# Reid_Orthotic_v2_PWR.net
KiCad netlist of a schematic drawn in Altium Designer
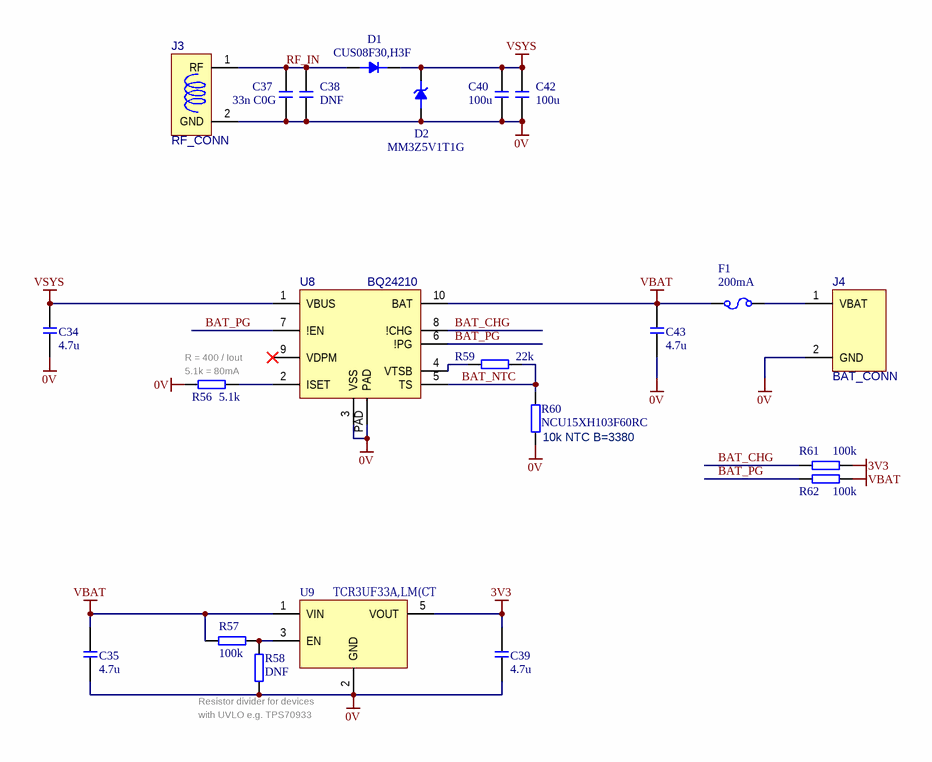
[diagram p0: Reid Orthotic v2 PWR.SchDoc]

(export (version "E")
  (design (tool "Eeschema 10.0.6"))
  (components
    (comp (ref "C34")
      (value "4.7u")
      (footprint "0603 CAP HD")
      (libsource (lib "zoo589 PCB Library") (part "Capacitor"))
    )
    (comp (ref "C35")
      (value "4.7u")
      (footprint "0603 CAP HD")
      (libsource (lib "zoo589 PCB Library") (part "Capacitor"))
    )
    (comp (ref "C37")
      (value "33n C0G")
      (footprint "0805 CAP")
      (libsource (lib "zoo589 PCB Library") (part "Capacitor"))
    )
    (comp (ref "C38")
      (value "DNF")
      (footprint "0805 CAP")
      (libsource (lib "zoo589 PCB Library") (part "Capacitor"))
    )
    (comp (ref "C39")
      (value "4.7u")
      (footprint "0603 CAP HD")
      (libsource (lib "zoo589 PCB Library") (part "Capacitor"))
    )
    (comp (ref "C40")
      (value "100u")
      (footprint "0805 CAP")
      (libsource (lib "zoo589 PCB Library") (part "Capacitor"))
    )
    (comp (ref "C42")
      (value "100u")
      (footprint "0805 CAP")
      (libsource (lib "zoo589 PCB Library") (part "Capacitor"))
    )
    (comp (ref "C43")
      (value "4.7u")
      (footprint "0603 CAP HD")
      (libsource (lib "zoo589 PCB Library") (part "Capacitor"))
    )
    (comp (ref "D1")
      (value "CUS08F30,H3F")
      (footprint "SOD-323")
      (libsource (lib "zoo589 PCB Library") (part "Diode"))
    )
    (comp (ref "D2")
      (value "MM3Z5V1T1G")
      (footprint "SOD-323")
      (libsource (lib "zoo589 PCB Library") (part "Diode Zener"))
    )
    (comp (ref "F1")
      (value "200mA")
      (footprint "0603 FUSE")
      (libsource (lib "zoo589 PCB Library") (part "Fuse"))
    )
    (comp (ref "J3")
      (value "RF_CONN")
      (footprint "RF_CONN")
      (libsource (lib "Reid Orthotic v2") (part "RF_CONN"))
    )
    (comp (ref "J4")
      (value "BAT_CONN")
      (footprint "BAT_CONN")
      (libsource (lib "Reid Orthotic v2") (part "BAT_CONN"))
    )
    (comp (ref "R56")
      (value "5.1k")
      (footprint "0402 RES HD")
      (libsource (lib "zoo589 PCB Library") (part "Resistor"))
    )
    (comp (ref "R57")
      (value "100k")
      (footprint "0402 RES HD")
      (libsource (lib "zoo589 PCB Library") (part "Resistor"))
    )
    (comp (ref "R58")
      (value "DNF")
      (footprint "0402 RES HD")
      (libsource (lib "zoo589 PCB Library") (part "Resistor"))
    )
    (comp (ref "R59")
      (value "22k")
      (footprint "0402 RES HD")
      (libsource (lib "zoo589 PCB Library") (part "Resistor"))
    )
    (comp (ref "R60")
      (value "NCU15XH103F60RC")
      (footprint "0402 RES HD")
      (libsource (lib "zoo589 PCB Library") (part "Resistor"))
    )
    (comp (ref "R61")
      (value "100k")
      (footprint "0402 RES HD")
      (libsource (lib "zoo589 PCB Library") (part "Resistor"))
    )
    (comp (ref "R62")
      (value "100k")
      (footprint "0402 RES HD")
      (libsource (lib "zoo589 PCB Library") (part "Resistor"))
    )
    (comp (ref "U8")
      (value "BQ24210")
      (footprint "BQ24210")
      (libsource (lib "CarbonCircuits Part Library") (part "BQ24210"))
    )
    (comp (ref "U9")
      (value "‎TCR3UF33A,LM(CT")
      (footprint "SOT23-5")
      (libsource (lib "zoo589 PCB Library") (part "MIC5504-x.xYM5"))
    )
  )
  (nets
    (net (code "1") (name "/BAT_CHG") (class "Default")
      (node (ref "R61") (pin "2") (pinfunction "2_2") (pintype "passive"))
      (node (ref "U8") (pin "8") (pinfunction "!CHG_8") (pintype "passive"))
    )
    (net (code "2") (name "/BAT_NTC") (class "Default")
      (node (ref "R59") (pin "2") (pinfunction "2_2") (pintype "passive"))
      (node (ref "R60") (pin "2") (pinfunction "2_2") (pintype "passive"))
      (node (ref "U8") (pin "5") (pinfunction "TS_5") (pintype "passive"))
    )
    (net (code "3") (name "/BAT_PG") (class "Default")
      (node (ref "R62") (pin "2") (pinfunction "2_2") (pintype "passive"))
      (node (ref "U8") (pin "6") (pinfunction "!PG_6") (pintype "passive"))
      (node (ref "U8") (pin "7") (pinfunction "!EN_7") (pintype "passive"))
    )
    (net (code "4") (name "/RF_IN") (class "Default")
      (node (ref "C37") (pin "2") (pinfunction "2_2") (pintype "passive"))
      (node (ref "C38") (pin "2") (pinfunction "2_2") (pintype "passive"))
      (node (ref "D1") (pin "A") (pinfunction "A_A") (pintype "passive"))
      (node (ref "J3") (pin "1") (pinfunction "RF_1") (pintype "passive"))
    )
    (net (code "5") (name "0V") (class "Default")
      (node (ref "C34") (pin "1") (pinfunction "1_1") (pintype "passive"))
      (node (ref "C35") (pin "1") (pinfunction "1_1") (pintype "passive"))
      (node (ref "C37") (pin "1") (pinfunction "1_1") (pintype "passive"))
      (node (ref "C38") (pin "1") (pinfunction "1_1") (pintype "passive"))
      (node (ref "C39") (pin "1") (pinfunction "1_1") (pintype "passive"))
      (node (ref "C40") (pin "1") (pinfunction "1_1") (pintype "passive"))
      (node (ref "C42") (pin "1") (pinfunction "1_1") (pintype "passive"))
      (node (ref "C43") (pin "1") (pinfunction "1_1") (pintype "passive"))
      (node (ref "D2") (pin "A") (pinfunction "A_A") (pintype "passive"))
      (node (ref "J3") (pin "2") (pinfunction "GND_2") (pintype "passive"))
      (node (ref "J4") (pin "2") (pinfunction "GND_2") (pintype "passive"))
      (node (ref "R56") (pin "2") (pinfunction "2_2") (pintype "passive"))
      (node (ref "R58") (pin "2") (pinfunction "2_2") (pintype "passive"))
      (node (ref "R60") (pin "1") (pinfunction "1_1") (pintype "passive"))
      (node (ref "U8") (pin "3") (pinfunction "VSS_3") (pintype "passive"))
      (node (ref "U8") (pin "PAD") (pinfunction "PAD_PAD") (pintype "passive"))
      (node (ref "U9") (pin "2") (pinfunction "GND_2") (pintype "passive"))
    )
    (net (code "6") (name "3V3") (class "Default")
      (node (ref "C39") (pin "2") (pinfunction "2_2") (pintype "passive"))
      (node (ref "R61") (pin "1") (pinfunction "1_1") (pintype "passive"))
      (node (ref "U9") (pin "5") (pinfunction "VOUT_5") (pintype "passive"))
    )
    (net (code "7") (name "Net-(J4-VBAT)") (class "Default")
      (node (ref "F1") (pin "1") (pinfunction "1_1") (pintype "passive"))
      (node (ref "J4") (pin "1") (pinfunction "VBAT_1") (pintype "passive"))
    )
    (net (code "8") (name "Net-(U8-ISET)") (class "Default")
      (node (ref "R56") (pin "1") (pinfunction "1_1") (pintype "passive"))
      (node (ref "U8") (pin "2") (pinfunction "ISET_2") (pintype "passive"))
    )
    (net (code "9") (name "Net-(U8-VTSB)") (class "Default")
      (node (ref "R59") (pin "1") (pinfunction "1_1") (pintype "passive"))
      (node (ref "U8") (pin "4") (pinfunction "VTSB_4") (pintype "passive"))
    )
    (net (code "10") (name "Net-(U9-EN)") (class "Default")
      (node (ref "R57") (pin "1") (pinfunction "1_1") (pintype "passive"))
      (node (ref "R58") (pin "1") (pinfunction "1_1") (pintype "passive"))
      (node (ref "U9") (pin "3") (pinfunction "EN_3") (pintype "passive"))
    )
    (net (code "11") (name "VBAT") (class "Default")
      (node (ref "C35") (pin "2") (pinfunction "2_2") (pintype "passive"))
      (node (ref "C43") (pin "2") (pinfunction "2_2") (pintype "passive"))
      (node (ref "F1") (pin "2") (pinfunction "2_2") (pintype "passive"))
      (node (ref "R57") (pin "2") (pinfunction "2_2") (pintype "passive"))
      (node (ref "R62") (pin "1") (pinfunction "1_1") (pintype "passive"))
      (node (ref "U8") (pin "10") (pinfunction "BAT_10") (pintype "passive"))
      (node (ref "U9") (pin "1") (pinfunction "VIN_1") (pintype "passive"))
    )
    (net (code "12") (name "VSYS") (class "Default")
      (node (ref "C34") (pin "2") (pinfunction "2_2") (pintype "passive"))
      (node (ref "C40") (pin "2") (pinfunction "2_2") (pintype "passive"))
      (node (ref "C42") (pin "2") (pinfunction "2_2") (pintype "passive"))
      (node (ref "D1") (pin "K") (pinfunction "K_K") (pintype "passive"))
      (node (ref "D2") (pin "K") (pinfunction "K_K") (pintype "passive"))
      (node (ref "U8") (pin "1") (pinfunction "VBUS_1") (pintype "passive"))
    )
    (net (code "13") (name "unconnected-(U8-VDPM-Pad9)") (class "Default")
      (node (ref "U8") (pin "9") (pinfunction "VDPM_9") (pintype "passive+no_connect"))
    )
  )
)
